# Urzeitcode_-_18F16Q41.net
KiCad netlist of a schematic drawn in EAGLE
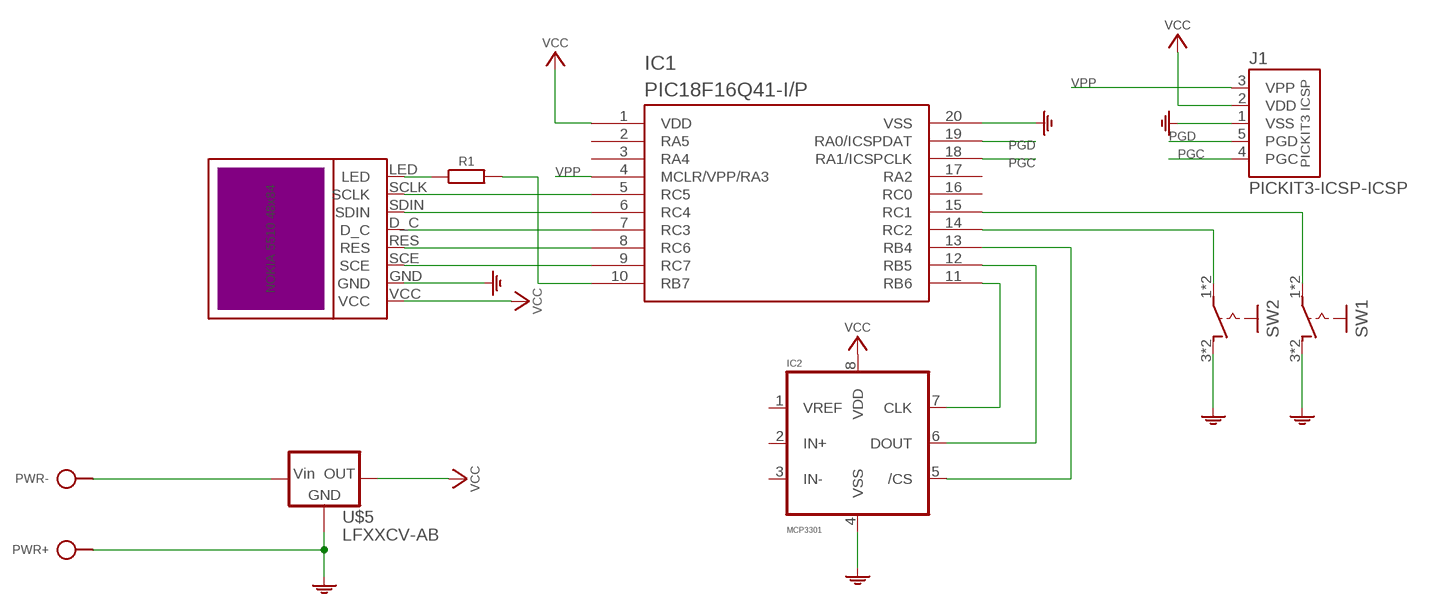
[diagram p0: schematic, sheet 1]

(export (version "E")
  (design (tool "Eeschema 10.0.6"))
  (components
    (comp (ref "IC1")
      (value "PIC18F16Q41-I/P")
      (footprint "eagle-import:DIL20-3_V")
      (libsource (lib "eagle-import") (part "PIC18F16Q41-I/P"))
    )
    (comp (ref "IC2")
      (value "MCP3301")
      (footprint "eagle-import:DIL08")
      (libsource (lib "eagle-import") (part "MCP3301"))
    )
    (comp (ref "J1")
      (value "PICKIT3-ICSP-ICSP")
      (footprint "eagle-import:PIC-ICSP")
      (libsource (lib "eagle-import") (part "PICKIT3-ICSP-ICSP"))
    )
    (comp (ref "PWR")
      (value "SPAD+-+-")
      (footprint "eagle-import:SPAD+-")
      (libsource (lib "eagle-import") (part "SPAD+-+-"))
    )
    (comp (ref "R1")
      (value "R-H0204/15-V")
      (footprint "eagle-import:0204_15-V")
      (libsource (lib "eagle-import") (part "R-H0204/15-V"))
    )
    (comp (ref "SW1")
      (value "PB-1P-1T2P1T")
      (footprint "eagle-import:PB-2P1T")
      (libsource (lib "eagle-import") (part "PB-1P-1T2P1T"))
    )
    (comp (ref "SW2")
      (value "PB-1P-1T2P1T")
      (footprint "eagle-import:PB-2P1T")
      (libsource (lib "eagle-import") (part "PB-1P-1T2P1T"))
    )
    (comp (ref "U$2")
      (value "NOKIA-5510-48X84-MODULE")
      (footprint "eagle-import:MOD-LCD5110")
      (libsource (lib "eagle-import") (part "NOKIA-5510-48X84-MODULE"))
    )
    (comp (ref "U$5")
      (value "LFXXCV-AB")
      (footprint "eagle-import:TO220AB")
      (libsource (lib "eagle-import") (part "LFXXCV-AB"))
    )
  )
  (nets
    (net (code "1") (name "/PGC") (class "Default")
      (node (ref "IC1") (pin "18") (pinfunction "RA1/ICSPCLK_18") (pintype "passive"))
      (node (ref "J1") (pin "4") (pinfunction "PGC_4") (pintype "passive"))
    )
    (net (code "2") (name "/PGD") (class "Default")
      (node (ref "IC1") (pin "19") (pinfunction "RA0/ICSPDAT_19") (pintype "passive"))
      (node (ref "J1") (pin "5") (pinfunction "PGD_5") (pintype "passive"))
    )
    (net (code "3") (name "/VPP") (class "Default")
      (node (ref "IC1") (pin "4") (pinfunction "MCLR/VPP/RA3_4") (pintype "passive"))
      (node (ref "J1") (pin "3") (pinfunction "VPP_3") (pintype "passive"))
    )
    (net (code "4") (name "GND") (class "Default")
      (node (ref "IC1") (pin "20") (pinfunction "VSS_20") (pintype "passive"))
      (node (ref "IC2") (pin "4") (pinfunction "VSS_4") (pintype "power_in"))
      (node (ref "J1") (pin "1") (pinfunction "VSS_1") (pintype "passive"))
      (node (ref "PWR") (pin "2") (pinfunction "P$1_2") (pintype "passive"))
      (node (ref "SW1") (pin "3") (pinfunction "S_3") (pintype "passive"))
      (node (ref "SW1") (pin "4") (pinfunction "S_4") (pintype "passive"))
      (node (ref "SW2") (pin "3") (pinfunction "S_3") (pintype "passive"))
      (node (ref "SW2") (pin "4") (pinfunction "S_4") (pintype "passive"))
      (node (ref "U$2") (pin "GND") (pinfunction "GND_GND") (pintype "passive"))
      (node (ref "U$5") (pin "2") (pinfunction "GND_2") (pintype "input"))
    )
    (net (code "5") (name "Net-(IC1-RB4)") (class "Default")
      (node (ref "IC1") (pin "13") (pinfunction "RB4_13") (pintype "passive"))
      (node (ref "IC2") (pin "5") (pinfunction "/CS_5") (pintype "input"))
    )
    (net (code "6") (name "Net-(IC1-RB5)") (class "Default")
      (node (ref "IC1") (pin "12") (pinfunction "RB5_12") (pintype "passive"))
      (node (ref "IC2") (pin "6") (pinfunction "DOUT_6") (pintype "passive"))
    )
    (net (code "7") (name "Net-(IC1-RB6)") (class "Default")
      (node (ref "IC1") (pin "11") (pinfunction "RB6_11") (pintype "passive"))
      (node (ref "IC2") (pin "7") (pinfunction "CLK_7") (pintype "output"))
    )
    (net (code "8") (name "Net-(IC1-RB7)") (class "Default")
      (node (ref "IC1") (pin "10") (pinfunction "RB7_10") (pintype "passive"))
      (node (ref "R1") (pin "2") (pinfunction "2_2") (pintype "passive"))
    )
    (net (code "9") (name "Net-(IC1-RC1)") (class "Default")
      (node (ref "IC1") (pin "15") (pinfunction "RC1_15") (pintype "passive"))
      (node (ref "SW1") (pin "1") (pinfunction "P_1") (pintype "passive"))
      (node (ref "SW1") (pin "2") (pinfunction "P_2") (pintype "passive"))
    )
    (net (code "10") (name "Net-(IC1-RC2)") (class "Default")
      (node (ref "IC1") (pin "14") (pinfunction "RC2_14") (pintype "passive"))
      (node (ref "SW2") (pin "1") (pinfunction "P_1") (pintype "passive"))
      (node (ref "SW2") (pin "2") (pinfunction "P_2") (pintype "passive"))
    )
    (net (code "11") (name "Net-(IC1-RC3)") (class "Default")
      (node (ref "IC1") (pin "7") (pinfunction "RC3_7") (pintype "passive"))
      (node (ref "U$2") (pin "D_C") (pinfunction "D_C_D_C") (pintype "passive"))
    )
    (net (code "12") (name "Net-(IC1-RC4)") (class "Default")
      (node (ref "IC1") (pin "6") (pinfunction "RC4_6") (pintype "passive"))
      (node (ref "U$2") (pin "SDIN") (pinfunction "SDIN_SDIN") (pintype "passive"))
    )
    (net (code "13") (name "Net-(IC1-RC5)") (class "Default")
      (node (ref "IC1") (pin "5") (pinfunction "RC5_5") (pintype "passive"))
      (node (ref "U$2") (pin "SCLK") (pinfunction "SCLK_SCLK") (pintype "passive"))
    )
    (net (code "14") (name "Net-(IC1-RC6)") (class "Default")
      (node (ref "IC1") (pin "8") (pinfunction "RC6_8") (pintype "passive"))
      (node (ref "U$2") (pin "RES") (pinfunction "RES_RES") (pintype "passive"))
    )
    (net (code "15") (name "Net-(IC1-RC7)") (class "Default")
      (node (ref "IC1") (pin "9") (pinfunction "RC7_9") (pintype "passive"))
      (node (ref "U$2") (pin "SCE") (pinfunction "SCE_SCE") (pintype "passive"))
    )
    (net (code "16") (name "Net-(PWRB-P$1)") (class "Default")
      (node (ref "PWR") (pin "1") (pinfunction "P$1_1") (pintype "passive"))
      (node (ref "U$5") (pin "1") (pinfunction "VIN_1") (pintype "input"))
    )
    (net (code "17") (name "Net-(R1-Pad1)") (class "Default")
      (node (ref "R1") (pin "1") (pinfunction "1_1") (pintype "passive"))
      (node (ref "U$2") (pin "LED") (pinfunction "LED_LED") (pintype "passive"))
    )
    (net (code "18") (name "VCC") (class "Default")
      (node (ref "IC1") (pin "1") (pinfunction "VDD_1") (pintype "passive"))
      (node (ref "IC2") (pin "8") (pinfunction "VDD_8") (pintype "power_in"))
      (node (ref "J1") (pin "2") (pinfunction "VDD_2") (pintype "passive"))
      (node (ref "U$2") (pin "VCC") (pinfunction "VCC_VCC") (pintype "passive"))
      (node (ref "U$5") (pin "3") (pinfunction "VOUT_3") (pintype "output"))
    )
    (net (code "19") (name "unconnected-(IC1-RA2-Pad17)") (class "Default")
      (node (ref "IC1") (pin "17") (pinfunction "RA2_17") (pintype "passive"))
    )
    (net (code "20") (name "unconnected-(IC1-RA4-Pad3)") (class "Default")
      (node (ref "IC1") (pin "3") (pinfunction "RA4_3") (pintype "passive"))
    )
    (net (code "21") (name "unconnected-(IC1-RA5-Pad2)") (class "Default")
      (node (ref "IC1") (pin "2") (pinfunction "RA5_2") (pintype "passive"))
    )
    (net (code "22") (name "unconnected-(IC1-RC0-Pad16)") (class "Default")
      (node (ref "IC1") (pin "16") (pinfunction "RC0_16") (pintype "passive"))
    )
    (net (code "23") (name "unconnected-(IC2-IN+-Pad2)") (class "Default")
      (node (ref "IC2") (pin "2") (pinfunction "IN+_2") (pintype "input"))
    )
    (net (code "24") (name "unconnected-(IC2-IN--Pad3)") (class "Default")
      (node (ref "IC2") (pin "3") (pinfunction "IN-_3") (pintype "input"))
    )
    (net (code "25") (name "unconnected-(IC2-VREF-Pad1)") (class "Default")
      (node (ref "IC2") (pin "1") (pinfunction "VREF_1") (pintype "input"))
    )
  )
)
